# PS1_USBC_Input_and_Buck.net
KiCad netlist of a schematic drawn in Altium Designer
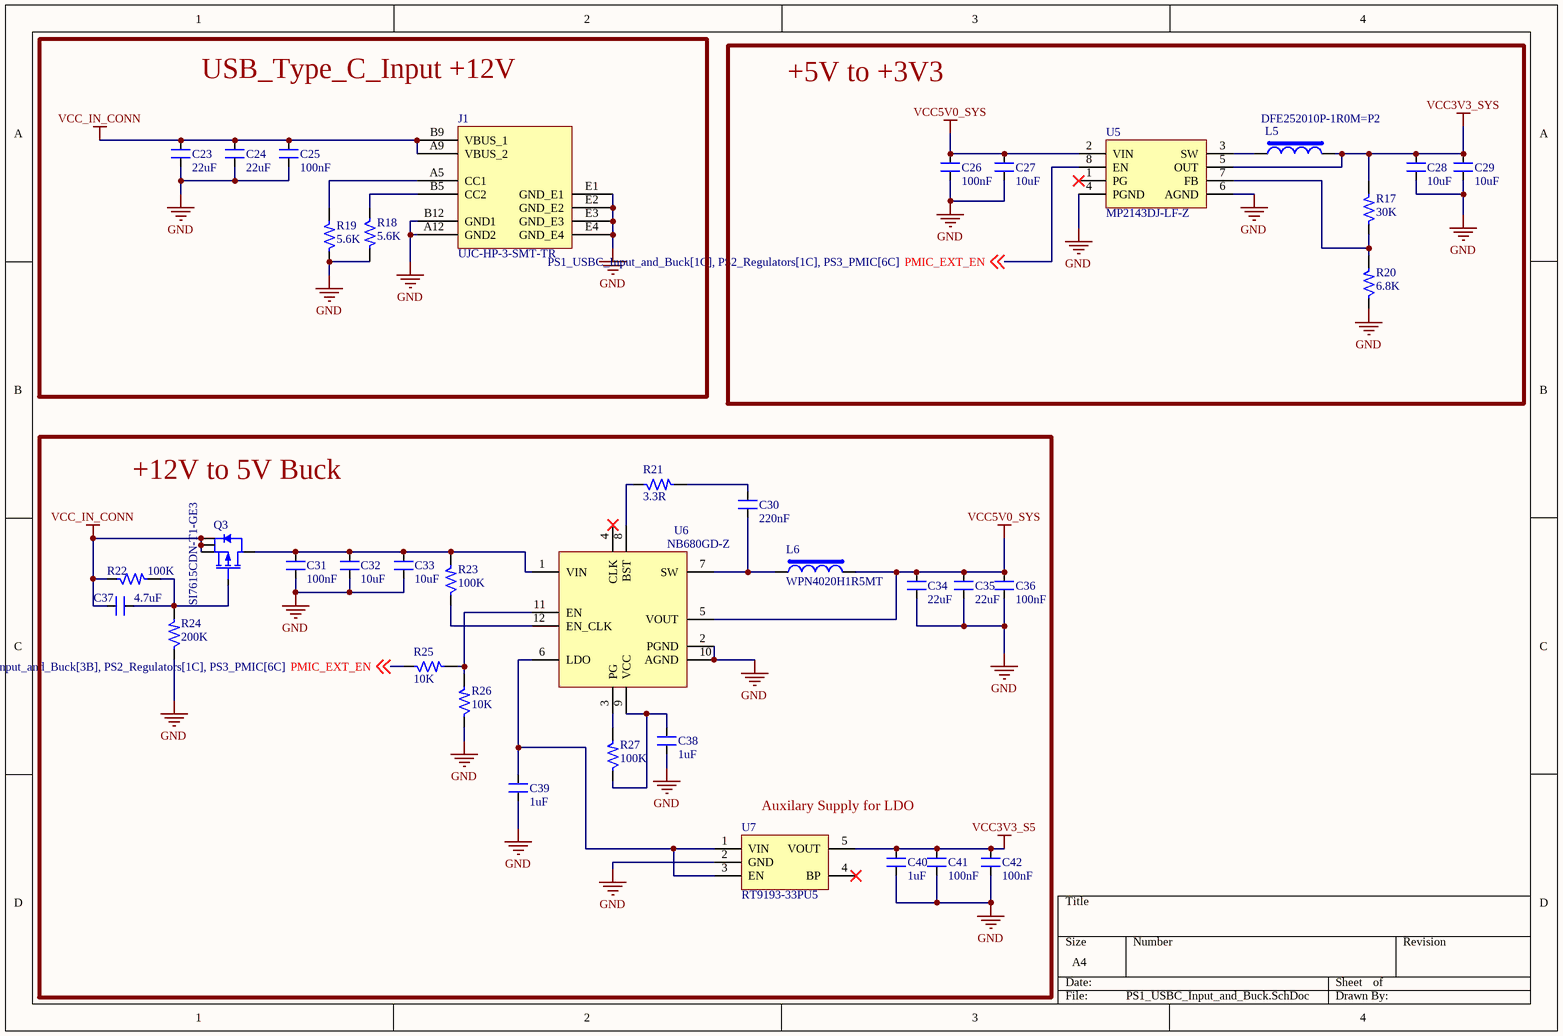
[diagram p0: PS1_USBC_Input_and_Buck.SchDoc]

(export (version "E")
  (design (tool "Eeschema 10.0.6"))
  (components
    (comp (ref "C23")
      (value "22uF")
      (footprint "CAP_0603")
      (description "22µF ±20% 10V Ceramic Capacitor X5R 0603 (1608 Metric)")
      (fields
        (field (name "MANUFACTURER") "Murata Electronics")
        (field (name "MANUFACTURER PART NUMBER") "GRM188R61A226ME15D")
      )
      (libsource (lib "EsteemPCB_SOM_Course_schlib") (part "CAP_22uF-10V-20%-0603"))
    )
    (comp (ref "C24")
      (value "22uF")
      (footprint "CAP_0603")
      (description "22µF ±20% 10V Ceramic Capacitor X5R 0603 (1608 Metric)")
      (fields
        (field (name "MANUFACTURER") "Murata Electronics")
        (field (name "MANUFACTURER PART NUMBER") "GRM188R61A226ME15D")
      )
      (libsource (lib "EsteemPCB_SOM_Course_schlib") (part "CAP_22uF-10V-20%-0603"))
    )
    (comp (ref "C25")
      (value "100nF")
      (footprint "CAP_0402")
      (description "0.1µF ±10% 25V Ceramic Capacitor X7R 0402 (1005 Metric)")
      (fields
        (field (name "MANUFACTURER") "Walsin Technology Corporation")
        (field (name "MANUFACTURER PART NUMBER") "0402B104K250CT")
      )
      (libsource (lib "EsteemPCB_SOM_Course_schlib") (part "CAP_100nF-25V-10%-0402"))
    )
    (comp (ref "C26")
      (value "100nF")
      (footprint "CAP_0402")
      (description "0.1µF ±10% 25V Ceramic Capacitor X7R 0402 (1005 Metric)")
      (fields
        (field (name "MANUFACTURER") "Walsin Technology Corporation")
        (field (name "MANUFACTURER PART NUMBER") "0402B104K250CT")
      )
      (libsource (lib "EsteemPCB_SOM_Course_schlib") (part "CAP_100nF-25V-10%-0402"))
    )
    (comp (ref "C27")
      (value "10uF")
      (footprint "CAP_0402")
      (description "10µF ±20% 10V Ceramic Capacitor X5R 0402 (1005 Metric)")
      (fields
        (field (name "MANUFACTURER PART NUMBER") "CL05A106MP5NUNC")
        (field (name "MANUFACTURER") "Samsung Electro-Mechanics")
      )
      (libsource (lib "EsteemPCB_SOM_Course_schlib") (part "CAP_10uF-10V-20%-0402"))
    )
    (comp (ref "C28")
      (value "10uF")
      (footprint "CAP_0402")
      (description "10µF ±20% 10V Ceramic Capacitor X5R 0402 (1005 Metric)")
      (fields
        (field (name "MANUFACTURER PART NUMBER") "CL05A106MP5NUNC")
        (field (name "MANUFACTURER") "Samsung Electro-Mechanics")
      )
      (libsource (lib "EsteemPCB_SOM_Course_schlib") (part "CAP_10uF-10V-20%-0402"))
    )
    (comp (ref "C29")
      (value "10uF")
      (footprint "CAP_0402")
      (description "10µF ±20% 10V Ceramic Capacitor X5R 0402 (1005 Metric)")
      (fields
        (field (name "MANUFACTURER PART NUMBER") "CL05A106MP5NUNC")
        (field (name "MANUFACTURER") "Samsung Electro-Mechanics")
      )
      (libsource (lib "EsteemPCB_SOM_Course_schlib") (part "CAP_10uF-10V-20%-0402"))
    )
    (comp (ref "C30")
      (value "220nF")
      (footprint "CAP_0402")
      (description "0.22µF ±10% 10V Ceramic Capacitor X7R 0402 (1005 Metric)")
      (fields
        (field (name "MANUFACTURER") "Samsung Electro-Mechanics")
        (field (name "MANUFACTURER PART NUMBER") "CL05B224KP5NNNC")
      )
      (libsource (lib "EsteemPCB_SOM_Course_schlib") (part "CAP_220nF-10V-10%-0402"))
    )
    (comp (ref "C31")
      (value "100nF")
      (footprint "CAP_0402")
      (description "0.1µF ±10% 25V Ceramic Capacitor X7R 0402 (1005 Metric)")
      (fields
        (field (name "MANUFACTURER") "Walsin Technology Corporation")
        (field (name "MANUFACTURER PART NUMBER") "0402B104K250CT")
      )
      (libsource (lib "EsteemPCB_SOM_Course_schlib") (part "CAP_100nF-25V-10%-0402"))
    )
    (comp (ref "C32")
      (value "10uF")
      (footprint "CAP_0402")
      (description "10µF ±20% 10V Ceramic Capacitor X5R 0402 (1005 Metric)")
      (fields
        (field (name "MANUFACTURER PART NUMBER") "CL05A106MP5NUNC")
        (field (name "MANUFACTURER") "Samsung Electro-Mechanics")
      )
      (libsource (lib "EsteemPCB_SOM_Course_schlib") (part "CAP_10uF-10V-20%-0402"))
    )
    (comp (ref "C33")
      (value "10uF")
      (footprint "CAP_0402")
      (description "10µF ±20% 10V Ceramic Capacitor X5R 0402 (1005 Metric)")
      (fields
        (field (name "MANUFACTURER PART NUMBER") "CL05A106MP5NUNC")
        (field (name "MANUFACTURER") "Samsung Electro-Mechanics")
      )
      (libsource (lib "EsteemPCB_SOM_Course_schlib") (part "CAP_10uF-10V-20%-0402"))
    )
    (comp (ref "C34")
      (value "22uF")
      (footprint "CAP_0603")
      (description "22µF ±20% 10V Ceramic Capacitor X5R 0603 (1608 Metric)")
      (fields
        (field (name "MANUFACTURER") "Murata Electronics")
        (field (name "MANUFACTURER PART NUMBER") "GRM188R61A226ME15D")
      )
      (libsource (lib "EsteemPCB_SOM_Course_schlib") (part "CAP_22uF-10V-20%-0603"))
    )
    (comp (ref "C35")
      (value "22uF")
      (footprint "CAP_0603")
      (description "22µF ±20% 10V Ceramic Capacitor X5R 0603 (1608 Metric)")
      (fields
        (field (name "MANUFACTURER") "Murata Electronics")
        (field (name "MANUFACTURER PART NUMBER") "GRM188R61A226ME15D")
      )
      (libsource (lib "EsteemPCB_SOM_Course_schlib") (part "CAP_22uF-10V-20%-0603"))
    )
    (comp (ref "C36")
      (value "100nF")
      (footprint "CAP_0402")
      (description "0.1µF ±10% 25V Ceramic Capacitor X7R 0402 (1005 Metric)")
      (fields
        (field (name "MANUFACTURER") "Walsin Technology Corporation")
        (field (name "MANUFACTURER PART NUMBER") "0402B104K250CT")
      )
      (libsource (lib "EsteemPCB_SOM_Course_schlib") (part "CAP_100nF-25V-10%-0402"))
    )
    (comp (ref "C37")
      (value "4.7uF")
      (footprint "CAP_0402")
      (description "4.7µF ±10% 10V Ceramic Capacitor X5R 0402 (1005 Metric)")
      (fields
        (field (name "MANUFACTURER") "Samsung Electro-Mechanics")
        (field (name "MANUFACTURER PART NUMBER") "CL05A475KP5NRNC")
      )
      (libsource (lib "EsteemPCB_SOM_Course_schlib") (part "CAP_4.7uF-10V-10%-0402"))
    )
    (comp (ref "C38")
      (value "1uF")
      (footprint "CAP_0402")
      (description "1µF ±10% 16V Ceramic Capacitor X5R 0402 (1005 Metric)")
      (fields
        (field (name "MANUFACTURER") "Knowles Novacap")
        (field (name "MANUFACTURER PART NUMBER") "0402BW105K160YT")
      )
      (libsource (lib "EsteemPCB_SOM_Course_schlib") (part "CAP_1uF-16V-10%-0402"))
    )
    (comp (ref "C39")
      (value "1uF")
      (footprint "CAP_0402")
      (description "1µF ±10% 16V Ceramic Capacitor X5R 0402 (1005 Metric)")
      (fields
        (field (name "MANUFACTURER") "Knowles Novacap")
        (field (name "MANUFACTURER PART NUMBER") "0402BW105K160YT")
      )
      (libsource (lib "EsteemPCB_SOM_Course_schlib") (part "CAP_1uF-16V-10%-0402"))
    )
    (comp (ref "C40")
      (value "1uF")
      (footprint "CAP_0402")
      (description "1µF ±10% 16V Ceramic Capacitor X5R 0402 (1005 Metric)")
      (fields
        (field (name "MANUFACTURER") "Knowles Novacap")
        (field (name "MANUFACTURER PART NUMBER") "0402BW105K160YT")
      )
      (libsource (lib "EsteemPCB_SOM_Course_schlib") (part "CAP_1uF-16V-10%-0402"))
    )
    (comp (ref "C41")
      (value "100nF")
      (footprint "CAP_0402")
      (description "0.1µF ±10% 25V Ceramic Capacitor X7R 0402 (1005 Metric)")
      (fields
        (field (name "MANUFACTURER") "Walsin Technology Corporation")
        (field (name "MANUFACTURER PART NUMBER") "0402B104K250CT")
      )
      (libsource (lib "EsteemPCB_SOM_Course_schlib") (part "CAP_100nF-25V-10%-0402"))
    )
    (comp (ref "C42")
      (value "100nF")
      (footprint "CAP_0402")
      (description "0.1µF ±10% 25V Ceramic Capacitor X7R 0402 (1005 Metric)")
      (fields
        (field (name "MANUFACTURER") "Walsin Technology Corporation")
        (field (name "MANUFACTURER PART NUMBER") "0402B104K250CT")
      )
      (libsource (lib "EsteemPCB_SOM_Course_schlib") (part "CAP_100nF-25V-10%-0402"))
    )
    (comp (ref "J1")
      (value "UJC-HP-3-SMT-TR")
      (footprint "CON6_48.4_UJC-HP-3-SMT-TR")
      (fields (field (name "MANUFACTURER") "CUI Devices"))
      (libsource (lib "EsteemPCB_SOM_Course_schlib") (part "CON-TYPEC_6X1-100-RA-TH"))
    )
    (comp (ref "L5")
      (value "DFE252010P-1R0M=P2")
      (footprint "IND_1008")
      (description "1µH Shielded Wirewound Inductor 3.8A 54mOhm Max 1008 (2520 Metric)")
      (fields (field (name "MANUFACTURER") "Murata Electronics"))
      (libsource (lib "EsteemPCB_SOM_Course_schlib") (part "IND_1uH-3.8A-20%-1008"))
    )
    (comp (ref "L6")
      (value "WPN4020H1R5MT")
      (footprint "IND_1616")
      (fields (field (name "MANUFACTURER") "Sunlord"))
      (libsource (lib "EsteemPCB_SOM_Course_schlib") (part "IND_1.5uH-6A-20%-SMD"))
    )
    (comp (ref "Q3")
      (value "SI7615CDN-T1-GE3")
      (footprint "PowerPAK_1212-8_SMD")
      (description "P-Channel 20V 35A (Tc) 33W (Tc) Surface Mount PowerPAK® 1212-8")
      (fields (field (name "MANUFACTURER") "Vishay Siliconix"))
      (libsource (lib "EsteemPCB_SOM_Course_schlib") (part "MOSFET-P_20V-35A-1212-8"))
    )
    (comp (ref "R17")
      (value "30K")
      (footprint "RES_0402")
      (fields
        (field (name "MANUFACTURER") "KOA Speer Electronics, Inc.")
        (field (name "MANUFACTURER PART NUMBER") "RK73H1ETTP3002F")
      )
      (libsource (lib "EsteemPCB_SOM_Course_schlib") (part "RES_30K-0.1W-1%-0402"))
    )
    (comp (ref "R18")
      (value "5.6K")
      (footprint "RES_0402")
      (fields
        (field (name "MANUFACTURER") "KOA Speer Electronics, Inc.")
        (field (name "MANUFACTURER PART NUMBER") "RK73H1ETTP5601F")
      )
      (libsource (lib "EsteemPCB_SOM_Course_schlib") (part "RES_5.6K-0.1W-1%-0402"))
    )
    (comp (ref "R19")
      (value "5.6K")
      (footprint "RES_0402")
      (fields
        (field (name "MANUFACTURER") "KOA Speer Electronics, Inc.")
        (field (name "MANUFACTURER PART NUMBER") "RK73H1ETTP5601F")
      )
      (libsource (lib "EsteemPCB_SOM_Course_schlib") (part "RES_5.6K-0.1W-1%-0402"))
    )
    (comp (ref "R20")
      (value "6.8K")
      (footprint "RES_0402")
      (description "6.8 kOhms ±1% 0.1W, 1/10W Chip Resistor 0402 (1005 Metric) Anti-Sulfur Thin Film")
      (fields
        (field (name "MANUFACTURER") "Vishay Beyschlag/Draloric/BC Components")
        (field (name "MANUFACTURER PART NUMBER") "MCS04020C6801FE000")
      )
      (libsource (lib "EsteemPCB_SOM_Course_schlib") (part "RES_6.8K-0.1W-1%-0402"))
    )
    (comp (ref "R21")
      (value "3.3R")
      (footprint "RES_0402")
      (fields
        (field (name "MANUFACTURER") "Panasonic Electronic Components")
        (field (name "MANUFACTURER PART NUMBER") "ERJ-U02F3R30X")
      )
      (libsource (lib "EsteemPCB_SOM_Course_schlib") (part "RES_3.3R-0.1W-1%-0402"))
    )
    (comp (ref "R22")
      (value "100K")
      (footprint "RES_0402")
      (description "100 kOhms ±1% 0.1W, 1/10W Chip Resistor 0402 (1005 Metric) Anti-Sulfur Thin Film")
      (fields
        (field (name "MANUFACTURER") "Vishay Beyschlag/Draloric/BC Components")
        (field (name "MANUFACTURER PART NUMBER") "MCS04020C1003FE000")
      )
      (libsource (lib "EsteemPCB_SOM_Course_schlib") (part "RES_100K-0.1W-1%-0402"))
    )
    (comp (ref "R23")
      (value "100K")
      (footprint "RES_0402")
      (description "100 kOhms ±1% 0.1W, 1/10W Chip Resistor 0402 (1005 Metric) Anti-Sulfur Thin Film")
      (fields
        (field (name "MANUFACTURER") "Vishay Beyschlag/Draloric/BC Components")
        (field (name "MANUFACTURER PART NUMBER") "MCS04020C1003FE000")
      )
      (libsource (lib "EsteemPCB_SOM_Course_schlib") (part "RES_100K-0.1W-1%-0402"))
    )
    (comp (ref "R24")
      (value "200K")
      (footprint "RES_0402")
      (description "200 kOhms ±1% 0.1W, 1/10W Chip Resistor 0402 (1005 Metric) Automotive AEC-Q200 Thick Film")
      (fields
        (field (name "MANUFACTURER") "Panasonic Electronic Components")
        (field (name "MANUFACTURER PART NUMBER") "ERJ-2RKF2003X")
      )
      (libsource (lib "EsteemPCB_SOM_Course_schlib") (part "RES_200K-0.1W-1%-0402"))
    )
    (comp (ref "R25")
      (value "10K")
      (footprint "RES_0402")
      (description "10 kOhms ±1% 0.1W, 1/10W Chip Resistor 0402 (1005 Metric) Anti-Sulfur Thin Film")
      (fields
        (field (name "MANUFACTURER") "Vishay Beyschlag/Draloric/BC Components")
        (field (name "MANUFACTURER PART NUMBER") "MCS04020C1002FE000")
      )
      (libsource (lib "EsteemPCB_SOM_Course_schlib") (part "RES_10K-0.1W-1%-0402"))
    )
    (comp (ref "R26")
      (value "10K")
      (footprint "RES_0402")
      (description "10 kOhms ±1% 0.1W, 1/10W Chip Resistor 0402 (1005 Metric) Anti-Sulfur Thin Film")
      (fields
        (field (name "MANUFACTURER") "Vishay Beyschlag/Draloric/BC Components")
        (field (name "MANUFACTURER PART NUMBER") "MCS04020C1002FE000")
      )
      (libsource (lib "EsteemPCB_SOM_Course_schlib") (part "RES_10K-0.1W-1%-0402"))
    )
    (comp (ref "R27")
      (value "100K")
      (footprint "RES_0402")
      (description "100 kOhms ±1% 0.1W, 1/10W Chip Resistor 0402 (1005 Metric) Anti-Sulfur Thin Film")
      (fields
        (field (name "MANUFACTURER") "Vishay Beyschlag/Draloric/BC Components")
        (field (name "MANUFACTURER PART NUMBER") "MCS04020C1003FE000")
      )
      (libsource (lib "EsteemPCB_SOM_Course_schlib") (part "RES_100K-0.1W-1%-0402"))
    )
    (comp (ref "U5")
      (value "MP2143DJ-LF-Z")
      (footprint "SOT23-8")
      (description "Switching Voltage Regulators 3A, 5.5V, 1.2MHz Sync Stp-Dwn Swtchr")
      (fields (field (name "MANUFACTURER") "Monolithic Power Systems (MPS)"))
      (libsource (lib "EsteemPCB_SOM_Course_schlib") (part "REG_0.6~5V-5.5V-3A-TSOT-23-8"))
    )
    (comp (ref "U6")
      (value "NB680GD-Z")
      (footprint "QFN-12_19_118X118_SMD")
      (description "Switching Voltage Regulators 26V Fixed 3.3 V-8A Sync Buck Converter")
      (fields (field (name "MANUFACTURER") "Monolithic Power Systems (MPS)"))
      (libsource (lib "EsteemPCB_SOM_Course_schlib") (part "REG_3.3V-26V-8A-QFN-12"))
    )
    (comp (ref "U7")
      (value "RT9193-33PU5")
      (footprint "SC70-5")
      (description "SC-70-5 Dropout Regulators(LDO) RoHS")
      (fields (field (name "MANUFACTURER") "Richtek Tech"))
      (libsource (lib "EsteemPCB_SOM_Course_schlib") (part "REG_3.3V-5.5V-300mA-SC-70-5"))
    )
  )
  (nets
    (net (code "1") (name "GND") (class "Default")
      (node (ref "C23") (pin "1") (pinfunction "1_1") (pintype "passive"))
      (node (ref "C24") (pin "1") (pinfunction "1_1") (pintype "passive"))
      (node (ref "C25") (pin "1") (pinfunction "1_1") (pintype "passive"))
      (node (ref "C26") (pin "1") (pinfunction "1_1") (pintype "passive"))
      (node (ref "C27") (pin "1") (pinfunction "1_1") (pintype "passive"))
      (node (ref "C28") (pin "1") (pinfunction "1_1") (pintype "passive"))
      (node (ref "C29") (pin "1") (pinfunction "1_1") (pintype "passive"))
      (node (ref "C31") (pin "1") (pinfunction "1_1") (pintype "passive"))
      (node (ref "C32") (pin "1") (pinfunction "1_1") (pintype "passive"))
      (node (ref "C33") (pin "1") (pinfunction "1_1") (pintype "passive"))
      (node (ref "C34") (pin "1") (pinfunction "1_1") (pintype "passive"))
      (node (ref "C35") (pin "1") (pinfunction "1_1") (pintype "passive"))
      (node (ref "C36") (pin "1") (pinfunction "1_1") (pintype "passive"))
      (node (ref "C38") (pin "1") (pinfunction "1_1") (pintype "passive"))
      (node (ref "C39") (pin "1") (pinfunction "1_1") (pintype "passive"))
      (node (ref "C40") (pin "1") (pinfunction "1_1") (pintype "passive"))
      (node (ref "C41") (pin "1") (pinfunction "1_1") (pintype "passive"))
      (node (ref "C42") (pin "1") (pinfunction "1_1") (pintype "passive"))
      (node (ref "J1") (pin "A12") (pinfunction "GND2_A12") (pintype "passive"))
      (node (ref "J1") (pin "B12") (pinfunction "GND1_B12") (pintype "passive"))
      (node (ref "J1") (pin "E1") (pinfunction "GND_E1_E1") (pintype "passive"))
      (node (ref "J1") (pin "E2") (pinfunction "GND_E2_E2") (pintype "passive"))
      (node (ref "J1") (pin "E3") (pinfunction "GND_E3_E3") (pintype "passive"))
      (node (ref "J1") (pin "E4") (pinfunction "GND_E4_E4") (pintype "passive"))
      (node (ref "R18") (pin "2") (pinfunction "2_2") (pintype "passive"))
      (node (ref "R19") (pin "1") (pinfunction "1_1") (pintype "passive"))
      (node (ref "R20") (pin "1") (pinfunction "1_1") (pintype "passive"))
      (node (ref "R24") (pin "1") (pinfunction "1_1") (pintype "passive"))
      (node (ref "R26") (pin "1") (pinfunction "1_1") (pintype "passive"))
      (node (ref "U5") (pin "4") (pinfunction "PGND_4") (pintype "passive"))
      (node (ref "U5") (pin "6") (pinfunction "AGND_6") (pintype "passive"))
      (node (ref "U6") (pin "10") (pinfunction "AGND_10") (pintype "passive"))
      (node (ref "U6") (pin "2") (pinfunction "PGND_2") (pintype "passive"))
      (node (ref "U7") (pin "2") (pinfunction "GND_2") (pintype "passive"))
    )
    (net (code "2") (name "Net-(C30-Pad2)") (class "Default")
      (node (ref "C30") (pin "2") (pinfunction "2_2") (pintype "passive"))
      (node (ref "R21") (pin "2") (pinfunction "2_2") (pintype "passive"))
    )
    (net (code "3") (name "Net-(J1-CC1)") (class "Default")
      (node (ref "J1") (pin "A5") (pinfunction "CC1_A5") (pintype "passive"))
      (node (ref "R19") (pin "2") (pinfunction "2_2") (pintype "passive"))
    )
    (net (code "4") (name "Net-(J1-CC2)") (class "Default")
      (node (ref "J1") (pin "B5") (pinfunction "CC2_B5") (pintype "passive"))
      (node (ref "R18") (pin "1") (pinfunction "1_1") (pintype "passive"))
    )
    (net (code "5") (name "Net-(Q3-D)") (class "Default")
      (node (ref "C31") (pin "2") (pinfunction "2_2") (pintype "passive"))
      (node (ref "C32") (pin "2") (pinfunction "2_2") (pintype "passive"))
      (node (ref "C33") (pin "2") (pinfunction "2_2") (pintype "passive"))
      (node (ref "Q3") (pin "5") (pinfunction "D_5") (pintype "passive"))
      (node (ref "R23") (pin "2") (pinfunction "2_2") (pintype "passive"))
      (node (ref "U6") (pin "1") (pinfunction "VIN_1") (pintype "passive"))
    )
    (net (code "6") (name "Net-(Q3-G)") (class "Default")
      (node (ref "C37") (pin "2") (pinfunction "2_2") (pintype "passive"))
      (node (ref "Q3") (pin "4") (pinfunction "G_4") (pintype "passive"))
      (node (ref "R22") (pin "2") (pinfunction "2_2") (pintype "passive"))
      (node (ref "R24") (pin "2") (pinfunction "2_2") (pintype "passive"))
    )
    (net (code "7") (name "Net-(U5-FB)") (class "Default")
      (node (ref "R17") (pin "1") (pinfunction "1_1") (pintype "passive"))
      (node (ref "R20") (pin "2") (pinfunction "2_2") (pintype "passive"))
      (node (ref "U5") (pin "7") (pinfunction "FB_7") (pintype "passive"))
    )
    (net (code "8") (name "Net-(U5-SW)") (class "Default")
      (node (ref "L5") (pin "1") (pinfunction "1_1") (pintype "passive"))
      (node (ref "U5") (pin "3") (pinfunction "SW_3") (pintype "passive"))
    )
    (net (code "9") (name "Net-(U6-BST)") (class "Default")
      (node (ref "R21") (pin "1") (pinfunction "1_1") (pintype "passive"))
      (node (ref "U6") (pin "8") (pinfunction "BST_8") (pintype "passive"))
    )
    (net (code "10") (name "Net-(U6-EN)") (class "Default")
      (node (ref "R25") (pin "2") (pinfunction "2_2") (pintype "passive"))
      (node (ref "R26") (pin "2") (pinfunction "2_2") (pintype "passive"))
      (node (ref "U6") (pin "11") (pinfunction "EN_11") (pintype "passive"))
    )
    (net (code "11") (name "Net-(U6-EN_CLK)") (class "Default")
      (node (ref "R23") (pin "1") (pinfunction "1_1") (pintype "passive"))
      (node (ref "U6") (pin "12") (pinfunction "EN_CLK_12") (pintype "passive"))
    )
    (net (code "12") (name "Net-(U6-LDO)") (class "Default")
      (node (ref "C39") (pin "2") (pinfunction "2_2") (pintype "passive"))
      (node (ref "U6") (pin "6") (pinfunction "LDO_6") (pintype "passive"))
      (node (ref "U7") (pin "1") (pinfunction "VIN_1") (pintype "passive"))
      (node (ref "U7") (pin "3") (pinfunction "EN_3") (pintype "passive"))
    )
    (net (code "13") (name "Net-(U6-PG)") (class "Default")
      (node (ref "R27") (pin "2") (pinfunction "2_2") (pintype "passive"))
      (node (ref "U6") (pin "3") (pinfunction "PG_3") (pintype "passive"))
    )
    (net (code "14") (name "Net-(U6-SW)") (class "Default")
      (node (ref "C30") (pin "1") (pinfunction "1_1") (pintype "passive"))
      (node (ref "L6") (pin "1") (pinfunction "1_1") (pintype "passive"))
      (node (ref "U6") (pin "7") (pinfunction "SW_7") (pintype "passive"))
    )
    (net (code "15") (name "Net-(U6-VCC)") (class "Default")
      (node (ref "C38") (pin "2") (pinfunction "2_2") (pintype "passive"))
      (node (ref "R27") (pin "1") (pinfunction "1_1") (pintype "passive"))
      (node (ref "U6") (pin "9") (pinfunction "VCC_9") (pintype "passive"))
    )
    (net (code "16") (name "PMIC_EXT_EN") (class "Default")
      (node (ref "R25") (pin "1") (pinfunction "1_1") (pintype "passive"))
      (node (ref "U5") (pin "8") (pinfunction "EN_8") (pintype "passive"))
    )
    (net (code "17") (name "VCC3V3_S5") (class "Default")
      (node (ref "C40") (pin "2") (pinfunction "2_2") (pintype "passive"))
      (node (ref "C41") (pin "2") (pinfunction "2_2") (pintype "passive"))
      (node (ref "C42") (pin "2") (pinfunction "2_2") (pintype "passive"))
      (node (ref "U7") (pin "5") (pinfunction "VOUT_5") (pintype "passive"))
    )
    (net (code "18") (name "VCC3V3_SYS") (class "Default")
      (node (ref "C28") (pin "2") (pinfunction "2_2") (pintype "passive"))
      (node (ref "C29") (pin "2") (pinfunction "2_2") (pintype "passive"))
      (node (ref "L5") (pin "2") (pinfunction "2_2") (pintype "passive"))
      (node (ref "R17") (pin "2") (pinfunction "2_2") (pintype "passive"))
      (node (ref "U5") (pin "5") (pinfunction "OUT_5") (pintype "passive"))
    )
    (net (code "19") (name "VCC5V0_SYS") (class "Default")
      (node (ref "C26") (pin "2") (pinfunction "2_2") (pintype "passive"))
      (node (ref "C27") (pin "2") (pinfunction "2_2") (pintype "passive"))
      (node (ref "C34") (pin "2") (pinfunction "2_2") (pintype "passive"))
      (node (ref "C35") (pin "2") (pinfunction "2_2") (pintype "passive"))
      (node (ref "C36") (pin "2") (pinfunction "2_2") (pintype "passive"))
      (node (ref "L6") (pin "2") (pinfunction "2_2") (pintype "passive"))
      (node (ref "U5") (pin "2") (pinfunction "VIN_2") (pintype "passive"))
      (node (ref "U6") (pin "5") (pinfunction "VOUT_5") (pintype "passive"))
    )
    (net (code "20") (name "VCC_IN_CONN") (class "Default")
      (node (ref "C23") (pin "2") (pinfunction "2_2") (pintype "passive"))
      (node (ref "C24") (pin "2") (pinfunction "2_2") (pintype "passive"))
      (node (ref "C25") (pin "2") (pinfunction "2_2") (pintype "passive"))
      (node (ref "C37") (pin "1") (pinfunction "1_1") (pintype "passive"))
      (node (ref "J1") (pin "A9") (pinfunction "VBUS_2_A9") (pintype "passive"))
      (node (ref "J1") (pin "B9") (pinfunction "VBUS_1_B9") (pintype "passive"))
      (node (ref "Q3") (pin "1") (pinfunction "S_1") (pintype "passive"))
      (node (ref "Q3") (pin "2") (pinfunction "S_2") (pintype "passive"))
      (node (ref "Q3") (pin "3") (pinfunction "S_3") (pintype "passive"))
      (node (ref "R22") (pin "1") (pinfunction "1_1") (pintype "passive"))
    )
    (net (code "21") (name "unconnected-(U5-PG-Pad1)") (class "Default")
      (node (ref "U5") (pin "1") (pinfunction "PG_1") (pintype "passive+no_connect"))
    )
    (net (code "22") (name "unconnected-(U6-CLK-Pad4)") (class "Default")
      (node (ref "U6") (pin "4") (pinfunction "CLK_4") (pintype "passive+no_connect"))
    )
    (net (code "23") (name "unconnected-(U7-BP-Pad4)") (class "Default")
      (node (ref "U7") (pin "4") (pinfunction "BP_4") (pintype "passive+no_connect"))
    )
  )
)
